# STM32F103.net
KiCad netlist of a schematic drawn in Altium Designer
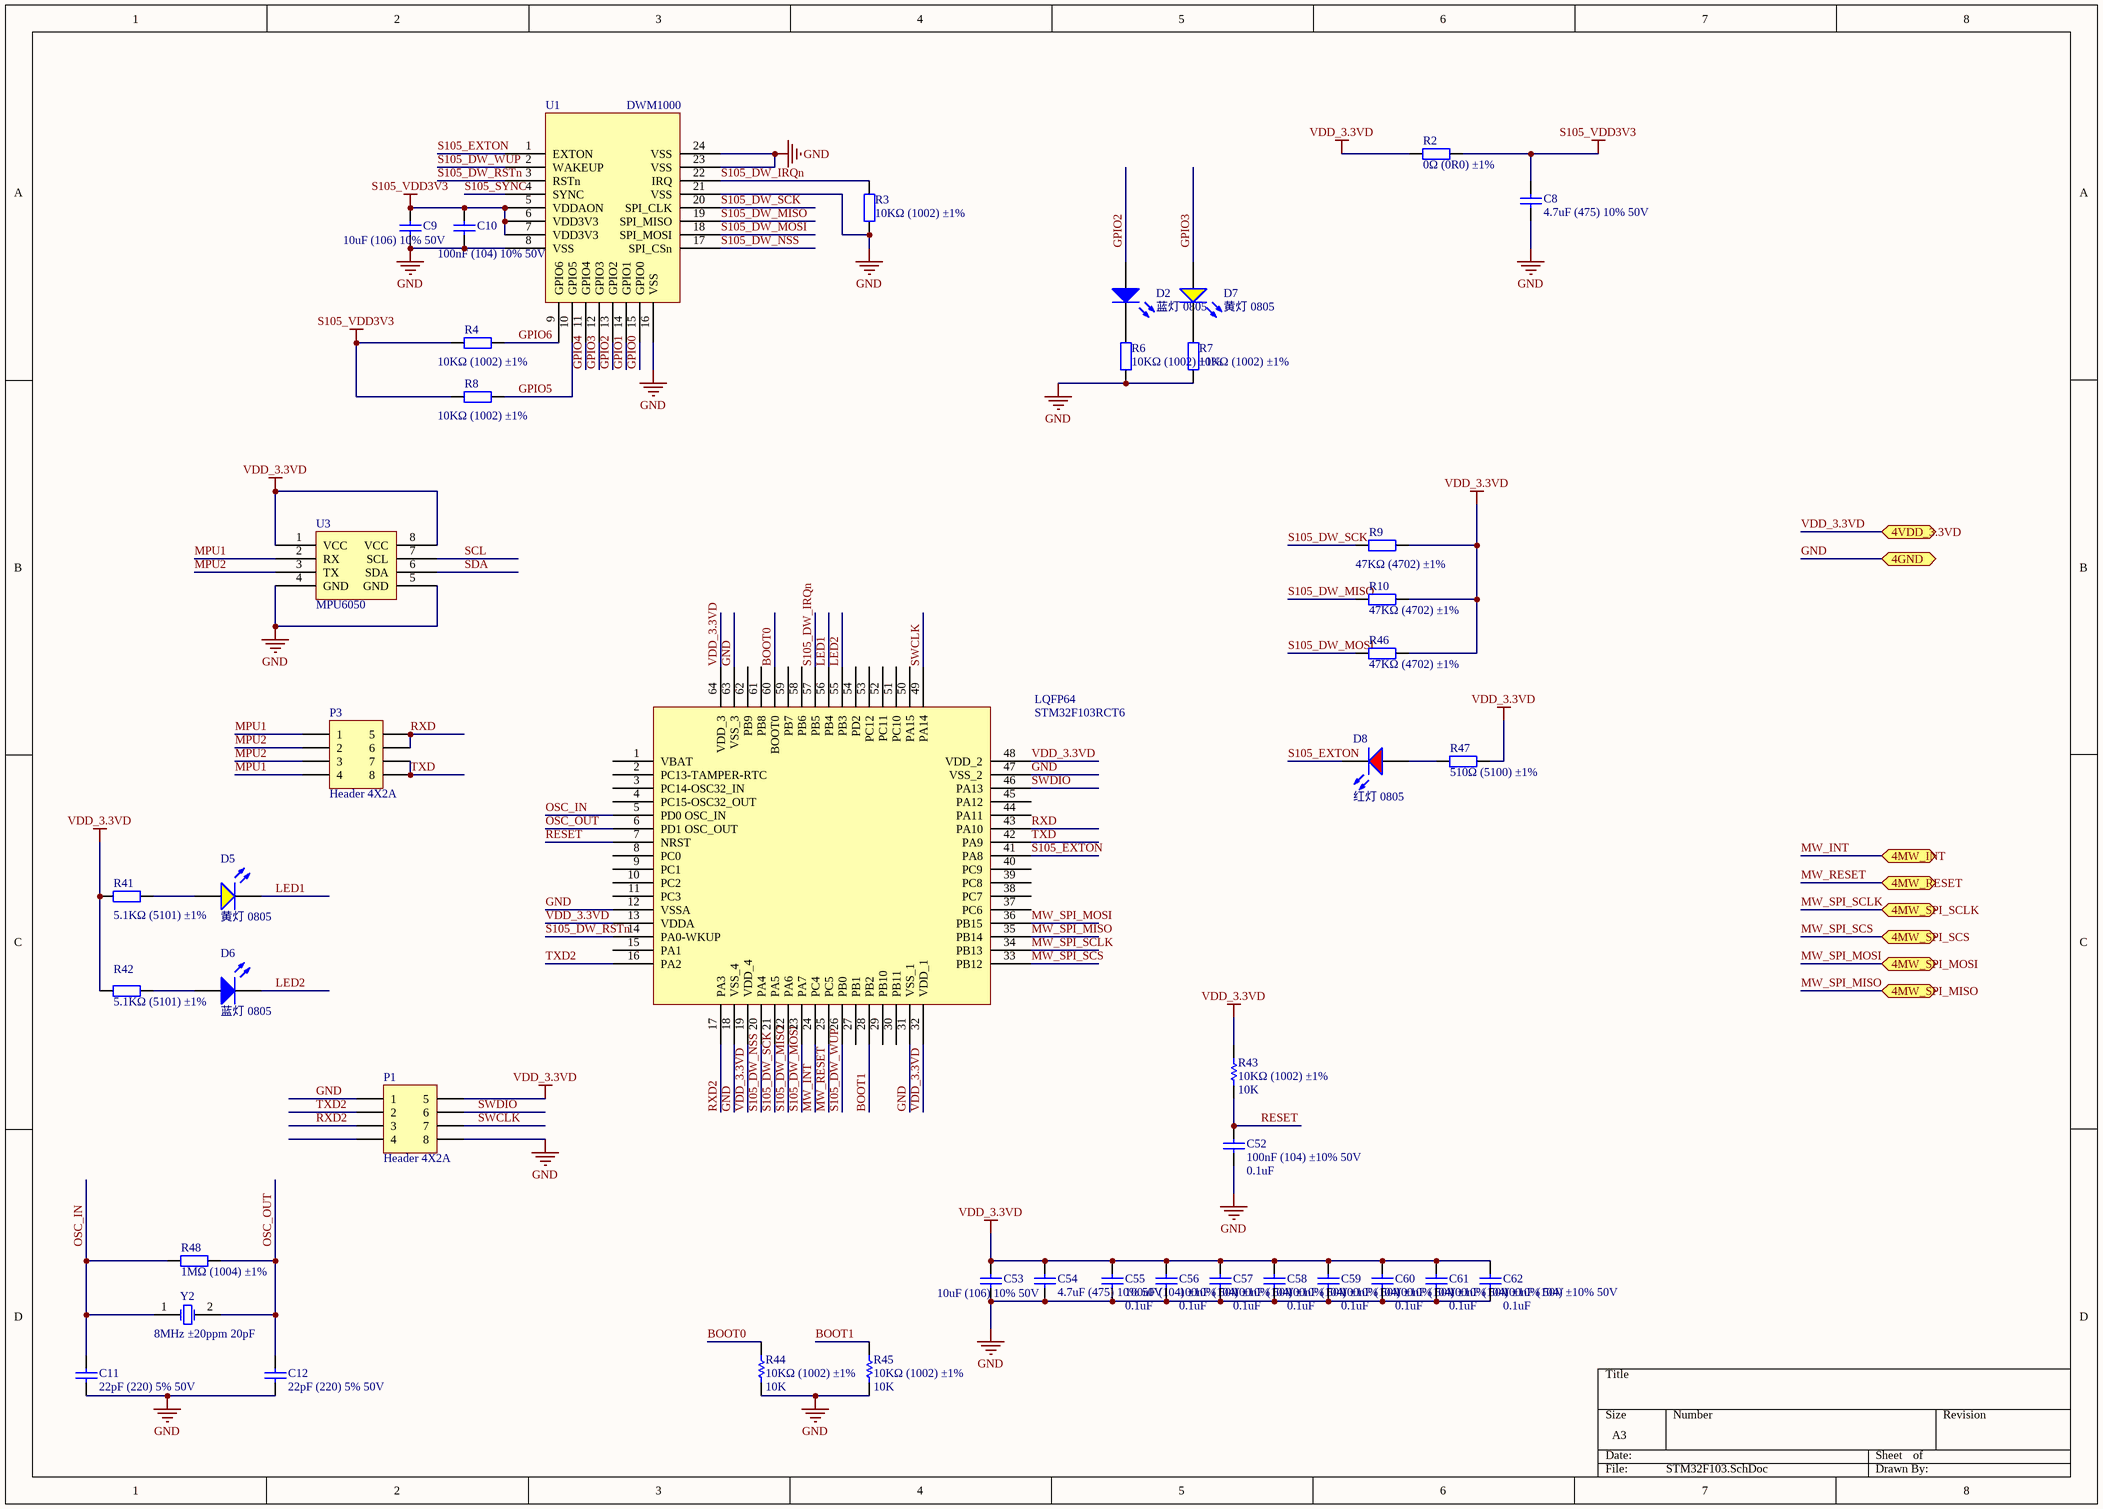
[diagram p0: STM32F103.SchDoc]

(export (version "E")
  (design (tool "Eeschema 10.0.6"))
  (components
    (comp (ref "C8")
      (value "4.7uF (475) 10% 50V")
      (footprint "1206_C")
      (description "贴片电容")
      (libsource (lib "Miscellaneous Devices LC") (part "1206 4.7uF (475) 10% 50V"))
    )
    (comp (ref "C9")
      (value "10uF (106) 10% 50V")
      (footprint "1206_C")
      (description "贴片电容")
      (libsource (lib "Miscellaneous Devices LC") (part "1206 10uF (106) 10% 50V"))
    )
    (comp (ref "C10")
      (value "100nF (104) 10% 50V")
      (footprint "0603_C")
      (description "贴片电容")
      (libsource (lib "Miscellaneous Devices LC") (part "0603 100nF (104) 10% 50V"))
    )
    (comp (ref "C11")
      (value "22pF (220) 5% 50V")
      (footprint "0603_C")
      (description "贴片电容")
      (libsource (lib "Miscellaneous Devices LC") (part "0603 22pF (220) 5% 50V"))
    )
    (comp (ref "C12")
      (value "22pF (220) 5% 50V")
      (footprint "0603_C")
      (description "贴片电容")
      (libsource (lib "Miscellaneous Devices LC") (part "0603 22pF (220) 5% 50V"))
    )
    (comp (ref "C52")
      (value "100nF (104) ±10% 50V")
      (footprint "1608[0603]")
      (description "Capacitor")
      (fields (field (name "ALTIUM_VALUE") "0.1uF") (field (name "PUBLISHER") "Altium Limited"))
      (libsource (lib "Miscellaneous Devices") (part "Cap"))
    )
    (comp (ref "C53")
      (value "10uF (106) 10% 50V")
      (footprint "1206_C")
      (description "贴片电容")
      (libsource (lib "Miscellaneous Devices LC") (part "1206 10uF (106) 10% 50V"))
    )
    (comp (ref "C54")
      (value "4.7uF (475) 10% 50V")
      (footprint "1206_C")
      (description "贴片电容")
      (libsource (lib "Miscellaneous Devices LC") (part "1206 4.7uF (475) 10% 50V"))
    )
    (comp (ref "C55")
      (value "100nF (104) ±10% 50V")
      (footprint "1608[0603]")
      (description "Capacitor")
      (fields (field (name "ALTIUM_VALUE") "0.1uF") (field (name "PUBLISHER") "Altium Limited"))
      (libsource (lib "Miscellaneous Devices") (part "Cap"))
    )
    (comp (ref "C56")
      (value "100nF (104) ±10% 50V")
      (footprint "1608[0603]")
      (description "Capacitor")
      (fields (field (name "ALTIUM_VALUE") "0.1uF") (field (name "PUBLISHER") "Altium Limited"))
      (libsource (lib "Miscellaneous Devices") (part "Cap"))
    )
    (comp (ref "C57")
      (value "100nF (104) ±10% 50V")
      (footprint "1608[0603]")
      (description "Capacitor")
      (fields (field (name "ALTIUM_VALUE") "0.1uF") (field (name "PUBLISHER") "Altium Limited"))
      (libsource (lib "Miscellaneous Devices") (part "Cap"))
    )
    (comp (ref "C58")
      (value "100nF (104) ±10% 50V")
      (footprint "1608[0603]")
      (description "Capacitor")
      (fields (field (name "ALTIUM_VALUE") "0.1uF") (field (name "PUBLISHER") "Altium Limited"))
      (libsource (lib "Miscellaneous Devices") (part "Cap"))
    )
    (comp (ref "C59")
      (value "100nF (104) ±10% 50V")
      (footprint "1608[0603]")
      (description "Capacitor")
      (fields (field (name "ALTIUM_VALUE") "0.1uF") (field (name "PUBLISHER") "Altium Limited"))
      (libsource (lib "Miscellaneous Devices") (part "Cap"))
    )
    (comp (ref "C60")
      (value "100nF (104) ±10% 50V")
      (footprint "1608[0603]")
      (description "Capacitor")
      (fields (field (name "ALTIUM_VALUE") "0.1uF") (field (name "PUBLISHER") "Altium Limited"))
      (libsource (lib "Miscellaneous Devices") (part "Cap"))
    )
    (comp (ref "C61")
      (value "100nF (104) ±10% 50V")
      (footprint "1608[0603]")
      (description "Capacitor")
      (fields (field (name "ALTIUM_VALUE") "0.1uF") (field (name "PUBLISHER") "Altium Limited"))
      (libsource (lib "Miscellaneous Devices") (part "Cap"))
    )
    (comp (ref "C62")
      (value "100nF (104) ±10% 50V")
      (footprint "1608[0603]")
      (description "Capacitor")
      (fields (field (name "ALTIUM_VALUE") "0.1uF") (field (name "PUBLISHER") "Altium Limited"))
      (libsource (lib "Miscellaneous Devices") (part "Cap"))
    )
    (comp (ref "D2")
      (value "蓝灯 0805")
      (footprint "0805_LED_S1")
      (description "发光二极管")
      (libsource (lib "Miscellaneous Devices LC") (part "0805 蓝灯"))
    )
    (comp (ref "D5")
      (value "黄灯 0805")
      (footprint "0805_LED_S1")
      (description "发光二极管")
      (libsource (lib "Miscellaneous Devices LC") (part "0805 黄灯"))
    )
    (comp (ref "D6")
      (value "蓝灯 0805")
      (footprint "0805_LED_S1")
      (description "发光二极管")
      (libsource (lib "Miscellaneous Devices LC") (part "0805 蓝灯"))
    )
    (comp (ref "D7")
      (value "黄灯 0805")
      (footprint "0805_LED_S1")
      (description "发光二极管")
      (libsource (lib "Miscellaneous Devices LC") (part "0805 黄灯"))
    )
    (comp (ref "D8")
      (value "红灯 0805")
      (footprint "0805_LED_S1")
      (description "发光二极管")
      (libsource (lib "Miscellaneous Devices LC") (part "0805 红灯"))
    )
    (comp (ref "LQFP64")
      (value "STM32F103RCT6")
      (footprint "LQFP64")
      (libsource (lib "LS_Schlib1") (part "STM32F103RCT6"))
    )
    (comp (ref "P1")
      (value "Header 4X2A")
      (footprint "HDR2X4_CEN")
      (description "Header, 4-Pin, Dual row")
      (fields (field (name "PUBLISHER") "Altium Limited"))
      (libsource (lib "Miscellaneous Connectors") (part "Header 4X2A"))
    )
    (comp (ref "P3")
      (value "Header 4X2A")
      (footprint "HDR2X4_CEN")
      (description "Header, 4-Pin, Dual row")
      (fields (field (name "PUBLISHER") "Altium Limited"))
      (libsource (lib "Miscellaneous Connectors") (part "Header 4X2A"))
    )
    (comp (ref "R2")
      (value "0Ω (0R0) ±1%")
      (footprint "1206_R")
      (description "贴片电阻")
      (libsource (lib "Miscellaneous Devices LC") (part "1206 0Ω (0R0) 1%"))
    )
    (comp (ref "R3")
      (value "10KΩ (1002) ±1%")
      (footprint "0603_R")
      (description "贴片电阻")
      (libsource (lib "Miscellaneous Devices LC") (part "0603 10KΩ (1002) 1%"))
    )
    (comp (ref "R4")
      (value "10KΩ (1002) ±1%")
      (footprint "0603_R")
      (description "贴片电阻")
      (libsource (lib "") (part "0603 10KΩ (1002) 1%_1"))
    )
    (comp (ref "R6")
      (value "10KΩ (1002) ±1%")
      (footprint "0603_R")
      (description "贴片电阻")
      (libsource (lib "Miscellaneous Devices LC") (part "0603 10KΩ (1002) 1%"))
    )
    (comp (ref "R7")
      (value "10KΩ (1002) ±1%")
      (footprint "0603_R")
      (description "贴片电阻")
      (libsource (lib "Miscellaneous Devices LC") (part "0603 10KΩ (1002) 1%"))
    )
    (comp (ref "R8")
      (value "10KΩ (1002) ±1%")
      (footprint "0603_R")
      (description "贴片电阻")
      (libsource (lib "") (part "0603 10KΩ (1002) 1%_1"))
    )
    (comp (ref "R9")
      (value "47KΩ (4702) ±1%")
      (footprint "0603_R")
      (description "贴片电阻")
      (libsource (lib "Miscellaneous Devices LC") (part "0603 47KΩ (4702) 1%"))
    )
    (comp (ref "R10")
      (value "47KΩ (4702) ±1%")
      (footprint "0603_R")
      (description "贴片电阻")
      (libsource (lib "Miscellaneous Devices LC") (part "0603 47KΩ (4702) 1%"))
    )
    (comp (ref "R41")
      (value "5.1KΩ (5101) ±1%")
      (footprint "0603_R")
      (description "贴片电阻")
      (libsource (lib "Miscellaneous Devices LC") (part "0603 5.1KΩ (5101) 1%"))
    )
    (comp (ref "R42")
      (value "5.1KΩ (5101) ±1%")
      (footprint "0603_R")
      (description "贴片电阻")
      (libsource (lib "Miscellaneous Devices LC") (part "0603 5.1KΩ (5101) 1%"))
    )
    (comp (ref "R43")
      (value "10KΩ (1002) ±1%")
      (footprint "1608[0603]")
      (description "Resistor")
      (fields (field (name "ALTIUM_VALUE") "10K") (field (name "PUBLISHER") "Altium Limited"))
      (libsource (lib "Miscellaneous Devices") (part "Res1"))
    )
    (comp (ref "R44")
      (value "10KΩ (1002) ±1%")
      (footprint "1608[0603]")
      (description "Resistor")
      (fields (field (name "ALTIUM_VALUE") "10K") (field (name "PUBLISHER") "Altium Limited"))
      (libsource (lib "Miscellaneous Devices") (part "Res1"))
    )
    (comp (ref "R45")
      (value "10KΩ (1002) ±1%")
      (footprint "1608[0603]")
      (description "Resistor")
      (fields (field (name "ALTIUM_VALUE") "10K") (field (name "PUBLISHER") "Altium Limited"))
      (libsource (lib "Miscellaneous Devices") (part "Res1"))
    )
    (comp (ref "R46")
      (value "47KΩ (4702) ±1%")
      (footprint "0603_R")
      (description "贴片电阻")
      (libsource (lib "Miscellaneous Devices LC") (part "0603 47KΩ (4702) 1%"))
    )
    (comp (ref "R47")
      (value "510Ω (5100) ±1%")
      (footprint "0603_R")
      (description "贴片电阻")
      (libsource (lib "Miscellaneous Devices LC") (part "0603 510Ω (5100) 1%"))
    )
    (comp (ref "R48")
      (value "1MΩ (1004) ±1%")
      (footprint "0603_R")
      (description "贴片电阻")
      (libsource (lib "Miscellaneous Devices LC") (part "0603 1MΩ (1004) 1%"))
    )
    (comp (ref "U1")
      (value "DWM1000")
      (footprint "DWM1000")
      (libsource (lib "UWB_Location") (part "DWM1000"))
    )
    (comp (ref "U3") (value "MPU6050") (footprint "MPU6050") (libsource (lib "LS_Schlib1") (part "MPU6050")))
    (comp (ref "Y2")
      (value "8MHz ±20ppm 20pF")
      (footprint "SMD-5032_2P")
      (description "贴片晶振")
      (libsource (lib "Miscellaneous Devices LC") (part "SMD-5032_2P 8MHz 20ppm 20pF"))
    )
  )
  (nets
    (net (code "1") (name "/BOOT0") (class "Default")
      (node (ref "LQFP64") (pin "60") (pinfunction "BOOT0_60") (pintype "passive"))
      (node (ref "R44") (pin "2") (pinfunction "2_2") (pintype "passive"))
    )
    (net (code "2") (name "/BOOT1") (class "Default")
      (node (ref "LQFP64") (pin "28") (pinfunction "PB2_28") (pintype "passive"))
      (node (ref "R45") (pin "2") (pinfunction "2_2") (pintype "passive"))
    )
    (net (code "3") (name "/GPIO0") (class "Default")
      (node (ref "U1") (pin "15") (pinfunction "GPIO0_15") (pintype "passive"))
    )
    (net (code "4") (name "/GPIO1") (class "Default")
      (node (ref "U1") (pin "14") (pinfunction "GPIO1_14") (pintype "passive"))
    )
    (net (code "5") (name "/GPIO2") (class "Default")
      (node (ref "D2") (pin "A") (pinfunction "A_A") (pintype "passive"))
      (node (ref "U1") (pin "13") (pinfunction "GPIO2_13") (pintype "passive"))
    )
    (net (code "6") (name "/GPIO3") (class "Default")
      (node (ref "D7") (pin "A") (pinfunction "A_A") (pintype "passive"))
      (node (ref "U1") (pin "12") (pinfunction "GPIO3_12") (pintype "passive"))
    )
    (net (code "7") (name "/GPIO4") (class "Default")
      (node (ref "U1") (pin "11") (pinfunction "GPIO4_11") (pintype "passive"))
    )
    (net (code "8") (name "/GPIO5") (class "Default")
      (node (ref "R8") (pin "2") (pinfunction "2_2") (pintype "passive"))
      (node (ref "U1") (pin "10") (pinfunction "GPIO5_10") (pintype "passive"))
    )
    (net (code "9") (name "/GPIO6") (class "Default")
      (node (ref "R4") (pin "2") (pinfunction "2_2") (pintype "passive"))
      (node (ref "U1") (pin "9") (pinfunction "GPIO6_9") (pintype "passive"))
    )
    (net (code "10") (name "/LED1") (class "Default")
      (node (ref "D5") (pin "K") (pinfunction "K_K") (pintype "passive"))
      (node (ref "LQFP64") (pin "56") (pinfunction "PB4_56") (pintype "passive"))
    )
    (net (code "11") (name "/LED2") (class "Default")
      (node (ref "D6") (pin "K") (pinfunction "K_K") (pintype "passive"))
      (node (ref "LQFP64") (pin "55") (pinfunction "PB3_55") (pintype "passive"))
    )
    (net (code "12") (name "/MPU1") (class "Default")
      (node (ref "P3") (pin "1") (pinfunction "1_1") (pintype "passive"))
      (node (ref "P3") (pin "4") (pinfunction "4_4") (pintype "passive"))
      (node (ref "U3") (pin "2") (pinfunction "RX_2") (pintype "passive"))
    )
    (net (code "13") (name "/MPU2") (class "Default")
      (node (ref "P3") (pin "2") (pinfunction "2_2") (pintype "passive"))
      (node (ref "P3") (pin "3") (pinfunction "3_3") (pintype "passive"))
      (node (ref "U3") (pin "3") (pinfunction "TX_3") (pintype "passive"))
    )
    (net (code "14") (name "/MW_INT") (class "Default")
      (node (ref "LQFP64") (pin "24") (pinfunction "PC4_24") (pintype "passive"))
    )
    (net (code "15") (name "/MW_RESET") (class "Default")
      (node (ref "LQFP64") (pin "25") (pinfunction "PC5_25") (pintype "passive"))
    )
    (net (code "16") (name "/MW_SPI_MISO") (class "Default")
      (node (ref "LQFP64") (pin "35") (pinfunction "PB14_35") (pintype "passive"))
    )
    (net (code "17") (name "/MW_SPI_MOSI") (class "Default")
      (node (ref "LQFP64") (pin "36") (pinfunction "PB15_36") (pintype "passive"))
    )
    (net (code "18") (name "/MW_SPI_SCLK") (class "Default")
      (node (ref "LQFP64") (pin "34") (pinfunction "PB13_34") (pintype "passive"))
    )
    (net (code "19") (name "/MW_SPI_SCS") (class "Default")
      (node (ref "LQFP64") (pin "33") (pinfunction "PB12_33") (pintype "passive"))
    )
    (net (code "20") (name "/OSC_IN") (class "Default")
      (node (ref "C11") (pin "2") (pinfunction "2_2") (pintype "passive"))
      (node (ref "LQFP64") (pin "5") (pinfunction "PD0_OSC_IN_5") (pintype "passive"))
      (node (ref "R48") (pin "1") (pinfunction "1_1") (pintype "passive"))
      (node (ref "Y2") (pin "1") (pinfunction "OSC1_1") (pintype "passive"))
    )
    (net (code "21") (name "/OSC_OUT") (class "Default")
      (node (ref "C12") (pin "2") (pinfunction "2_2") (pintype "passive"))
      (node (ref "LQFP64") (pin "6") (pinfunction "PD1_OSC_OUT_6") (pintype "passive"))
      (node (ref "R48") (pin "2") (pinfunction "2_2") (pintype "passive"))
      (node (ref "Y2") (pin "2") (pinfunction "OSC2_2") (pintype "passive"))
    )
    (net (code "22") (name "/RESET") (class "Default")
      (node (ref "C52") (pin "2") (pinfunction "2_2") (pintype "passive"))
      (node (ref "LQFP64") (pin "7") (pinfunction "NRST_7") (pintype "passive"))
      (node (ref "R43") (pin "1") (pinfunction "1_1") (pintype "passive"))
    )
    (net (code "23") (name "/RXD") (class "Default")
      (node (ref "LQFP64") (pin "43") (pinfunction "PA10_43") (pintype "passive"))
      (node (ref "P3") (pin "5") (pinfunction "5_5") (pintype "passive"))
      (node (ref "P3") (pin "6") (pinfunction "6_6") (pintype "passive"))
    )
    (net (code "24") (name "/RXD2") (class "Default")
      (node (ref "LQFP64") (pin "17") (pinfunction "PA3_17") (pintype "passive"))
      (node (ref "P1") (pin "3") (pinfunction "3_3") (pintype "passive"))
    )
    (net (code "25") (name "/S105_DW_IRQn") (class "Default")
      (node (ref "LQFP64") (pin "57") (pinfunction "PB5_57") (pintype "passive"))
      (node (ref "R3") (pin "2") (pinfunction "2_2") (pintype "passive"))
      (node (ref "U1") (pin "22") (pinfunction "IRQ_22") (pintype "passive"))
    )
    (net (code "26") (name "/S105_DW_MISO") (class "Default")
      (node (ref "LQFP64") (pin "22") (pinfunction "PA6_22") (pintype "passive"))
      (node (ref "R10") (pin "1") (pinfunction "1_1") (pintype "passive"))
      (node (ref "U1") (pin "19") (pinfunction "SPI_MISO_19") (pintype "passive"))
    )
    (net (code "27") (name "/S105_DW_MOSI") (class "Default")
      (node (ref "LQFP64") (pin "23") (pinfunction "PA7_23") (pintype "passive"))
      (node (ref "R46") (pin "1") (pinfunction "1_1") (pintype "passive"))
      (node (ref "U1") (pin "18") (pinfunction "SPI_MOSI_18") (pintype "passive"))
    )
    (net (code "28") (name "/S105_DW_NSS") (class "Default")
      (node (ref "LQFP64") (pin "20") (pinfunction "PA4_20") (pintype "passive"))
      (node (ref "U1") (pin "17") (pinfunction "SPI_CSn_17") (pintype "passive"))
    )
    (net (code "29") (name "/S105_DW_RSTn") (class "Default")
      (node (ref "LQFP64") (pin "14") (pinfunction "PA0-WKUP_14") (pintype "passive"))
      (node (ref "U1") (pin "3") (pinfunction "RSTn_3") (pintype "passive"))
    )
    (net (code "30") (name "/S105_DW_SCK") (class "Default")
      (node (ref "LQFP64") (pin "21") (pinfunction "PA5_21") (pintype "passive"))
      (node (ref "R9") (pin "1") (pinfunction "1_1") (pintype "passive"))
      (node (ref "U1") (pin "20") (pinfunction "SPI_CLK_20") (pintype "passive"))
    )
    (net (code "31") (name "/S105_DW_WUP") (class "Default")
      (node (ref "LQFP64") (pin "26") (pinfunction "PB0_26") (pintype "passive"))
      (node (ref "U1") (pin "2") (pinfunction "WAKEUP_2") (pintype "passive"))
    )
    (net (code "32") (name "/S105_EXTON") (class "Default")
      (node (ref "D8") (pin "K") (pinfunction "K_K") (pintype "passive"))
      (node (ref "LQFP64") (pin "41") (pinfunction "PA8_41") (pintype "passive"))
      (node (ref "U1") (pin "1") (pinfunction "EXTON_1") (pintype "passive"))
    )
    (net (code "33") (name "/S105_SYNC") (class "Default")
      (node (ref "U1") (pin "4") (pinfunction "SYNC_4") (pintype "passive"))
    )
    (net (code "34") (name "/SCL") (class "Default")
      (node (ref "U3") (pin "7") (pinfunction "SCL_7") (pintype "passive"))
    )
    (net (code "35") (name "/SDA") (class "Default")
      (node (ref "U3") (pin "6") (pinfunction "SDA_6") (pintype "passive"))
    )
    (net (code "36") (name "/SWCLK") (class "Default")
      (node (ref "LQFP64") (pin "49") (pinfunction "PA14_49") (pintype "passive"))
      (node (ref "P1") (pin "7") (pinfunction "7_7") (pintype "passive"))
    )
    (net (code "37") (name "/SWDIO") (class "Default")
      (node (ref "LQFP64") (pin "46") (pinfunction "PA13_46") (pintype "passive"))
      (node (ref "P1") (pin "6") (pinfunction "6_6") (pintype "passive"))
    )
    (net (code "38") (name "/TXD") (class "Default")
      (node (ref "LQFP64") (pin "42") (pinfunction "PA9_42") (pintype "passive"))
      (node (ref "P3") (pin "7") (pinfunction "7_7") (pintype "passive"))
      (node (ref "P3") (pin "8") (pinfunction "8_8") (pintype "passive"))
    )
    (net (code "39") (name "/TXD2") (class "Default")
      (node (ref "LQFP64") (pin "16") (pinfunction "PA2_16") (pintype "passive"))
      (node (ref "P1") (pin "2") (pinfunction "2_2") (pintype "passive"))
    )
    (net (code "40") (name "GND") (class "Default")
      (node (ref "C10") (pin "1") (pinfunction "1_1") (pintype "passive"))
      (node (ref "C11") (pin "1") (pinfunction "1_1") (pintype "passive"))
      (node (ref "C12") (pin "1") (pinfunction "1_1") (pintype "passive"))
      (node (ref "C52") (pin "1") (pinfunction "1_1") (pintype "passive"))
      (node (ref "C53") (pin "1") (pinfunction "1_1") (pintype "passive"))
      (node (ref "C54") (pin "1") (pinfunction "1_1") (pintype "passive"))
      (node (ref "C55") (pin "1") (pinfunction "1_1") (pintype "passive"))
      (node (ref "C56") (pin "1") (pinfunction "1_1") (pintype "passive"))
      (node (ref "C57") (pin "1") (pinfunction "1_1") (pintype "passive"))
      (node (ref "C58") (pin "1") (pinfunction "1_1") (pintype "passive"))
      (node (ref "C59") (pin "1") (pinfunction "1_1") (pintype "passive"))
      (node (ref "C60") (pin "1") (pinfunction "1_1") (pintype "passive"))
      (node (ref "C61") (pin "1") (pinfunction "1_1") (pintype "passive"))
      (node (ref "C62") (pin "1") (pinfunction "1_1") (pintype "passive"))
      (node (ref "C8") (pin "1") (pinfunction "1_1") (pintype "passive"))
      (node (ref "C9") (pin "1") (pinfunction "1_1") (pintype "passive"))
      (node (ref "LQFP64") (pin "12") (pinfunction "VSSA_12") (pintype "passive"))
      (node (ref "LQFP64") (pin "18") (pinfunction "VSS_4_18") (pintype "passive"))
      (node (ref "LQFP64") (pin "31") (pinfunction "VSS_1_31") (pintype "passive"))
      (node (ref "LQFP64") (pin "47") (pinfunction "VSS_2_47") (pintype "passive"))
      (node (ref "LQFP64") (pin "63") (pinfunction "VSS_3_63") (pintype "passive"))
      (node (ref "P1") (pin "1") (pinfunction "1_1") (pintype "passive"))
      (node (ref "P1") (pin "8") (pinfunction "8_8") (pintype "passive"))
      (node (ref "R3") (pin "1") (pinfunction "1_1") (pintype "passive"))
      (node (ref "R44") (pin "1") (pinfunction "1_1") (pintype "passive"))
      (node (ref "R45") (pin "1") (pinfunction "1_1") (pintype "passive"))
      (node (ref "R6") (pin "1") (pinfunction "1_1") (pintype "passive"))
      (node (ref "R7") (pin "1") (pinfunction "1_1") (pintype "passive"))
      (node (ref "U1") (pin "16") (pinfunction "VSS_16") (pintype "passive"))
      (node (ref "U1") (pin "21") (pinfunction "VSS_21") (pintype "passive"))
      (node (ref "U1") (pin "23") (pinfunction "VSS_23") (pintype "passive"))
      (node (ref "U1") (pin "24") (pinfunction "VSS_24") (pintype "passive"))
      (node (ref "U1") (pin "8") (pinfunction "VSS_8") (pintype "passive"))
      (node (ref "U3") (pin "4") (pinfunction "GND_4") (pintype "passive"))
      (node (ref "U3") (pin "5") (pinfunction "GND_5") (pintype "passive"))
    )
    (net (code "41") (name "Net-(D2-PadK)") (class "Default")
      (node (ref "D2") (pin "K") (pinfunction "K_K") (pintype "passive"))
      (node (ref "R6") (pin "2") (pinfunction "2_2") (pintype "passive"))
    )
    (net (code "42") (name "Net-(D5-PadA)") (class "Default")
      (node (ref "D5") (pin "A") (pinfunction "A_A") (pintype "passive"))
      (node (ref "R41") (pin "2") (pinfunction "2_2") (pintype "passive"))
    )
    (net (code "43") (name "Net-(D6-PadA)") (class "Default")
      (node (ref "D6") (pin "A") (pinfunction "A_A") (pintype "passive"))
      (node (ref "R42") (pin "2") (pinfunction "2_2") (pintype "passive"))
    )
    (net (code "44") (name "Net-(D7-PadK)") (class "Default")
      (node (ref "D7") (pin "K") (pinfunction "K_K") (pintype "passive"))
      (node (ref "R7") (pin "2") (pinfunction "2_2") (pintype "passive"))
    )
    (net (code "45") (name "Net-(D8-PadA)") (class "Default")
      (node (ref "D8") (pin "A") (pinfunction "A_A") (pintype "passive"))
      (node (ref "R47") (pin "1") (pinfunction "1_1") (pintype "passive"))
    )
    (net (code "46") (name "S105_VDD3V3") (class "Default")
      (node (ref "C10") (pin "2") (pinfunction "2_2") (pintype "passive"))
      (node (ref "C8") (pin "2") (pinfunction "2_2") (pintype "passive"))
      (node (ref "C9") (pin "2") (pinfunction "2_2") (pintype "passive"))
      (node (ref "R2") (pin "2") (pinfunction "2_2") (pintype "passive"))
      (node (ref "R4") (pin "1") (pinfunction "1_1") (pintype "passive"))
      (node (ref "R8") (pin "1") (pinfunction "1_1") (pintype "passive"))
      (node (ref "U1") (pin "5") (pinfunction "VDDAON_5") (pintype "passive"))
      (node (ref "U1") (pin "6") (pinfunction "VDD3V3_6") (pintype "passive"))
      (node (ref "U1") (pin "7") (pinfunction "VDD3V3_7") (pintype "passive"))
    )
    (net (code "47") (name "VDD_3.3VD") (class "Default")
      (node (ref "C53") (pin "2") (pinfunction "2_2") (pintype "passive"))
      (node (ref "C54") (pin "2") (pinfunction "2_2") (pintype "passive"))
      (node (ref "C55") (pin "2") (pinfunction "2_2") (pintype "passive"))
      (node (ref "C56") (pin "2") (pinfunction "2_2") (pintype "passive"))
      (node (ref "C57") (pin "2") (pinfunction "2_2") (pintype "passive"))
      (node (ref "C58") (pin "2") (pinfunction "2_2") (pintype "passive"))
      (node (ref "C59") (pin "2") (pinfunction "2_2") (pintype "passive"))
      (node (ref "C60") (pin "2") (pinfunction "2_2") (pintype "passive"))
      (node (ref "C61") (pin "2") (pinfunction "2_2") (pintype "passive"))
      (node (ref "C62") (pin "2") (pinfunction "2_2") (pintype "passive"))
      (node (ref "LQFP64") (pin "13") (pinfunction "VDDA_13") (pintype "passive"))
      (node (ref "LQFP64") (pin "19") (pinfunction "VDD_4_19") (pintype "passive"))
      (node (ref "LQFP64") (pin "32") (pinfunction "VDD_1_32") (pintype "passive"))
      (node (ref "LQFP64") (pin "48") (pinfunction "VDD_2_48") (pintype "passive"))
      (node (ref "LQFP64") (pin "64") (pinfunction "VDD_3_64") (pintype "passive"))
      (node (ref "P1") (pin "5") (pinfunction "5_5") (pintype "passive"))
      (node (ref "R10") (pin "2") (pinfunction "2_2") (pintype "passive"))
      (node (ref "R2") (pin "1") (pinfunction "1_1") (pintype "passive"))
      (node (ref "R41") (pin "1") (pinfunction "1_1") (pintype "passive"))
      (node (ref "R42") (pin "1") (pinfunction "1_1") (pintype "passive"))
      (node (ref "R43") (pin "2") (pinfunction "2_2") (pintype "passive"))
      (node (ref "R46") (pin "2") (pinfunction "2_2") (pintype "passive"))
      (node (ref "R47") (pin "2") (pinfunction "2_2") (pintype "passive"))
      (node (ref "R9") (pin "2") (pinfunction "2_2") (pintype "passive"))
      (node (ref "U3") (pin "1") (pinfunction "VCC_1") (pintype "passive"))
      (node (ref "U3") (pin "8") (pinfunction "VCC_8") (pintype "passive"))
    )
    (net (code "48") (name "unconnected-(LQFP64-PA1-Pad15)") (class "Default")
      (node (ref "LQFP64") (pin "15") (pinfunction "PA1_15") (pintype "passive"))
    )
    (net (code "49") (name "unconnected-(LQFP64-PA11-Pad44)") (class "Default")
      (node (ref "LQFP64") (pin "44") (pinfunction "PA11_44") (pintype "passive"))
    )
    (net (code "50") (name "unconnected-(LQFP64-PA12-Pad45)") (class "Default")
      (node (ref "LQFP64") (pin "45") (pinfunction "PA12_45") (pintype "passive"))
    )
    (net (code "51") (name "unconnected-(LQFP64-PA15-Pad50)") (class "Default")
      (node (ref "LQFP64") (pin "50") (pinfunction "PA15_50") (pintype "passive"))
    )
    (net (code "52") (name "unconnected-(LQFP64-PB1-Pad27)") (class "Default")
      (node (ref "LQFP64") (pin "27") (pinfunction "PB1_27") (pintype "passive"))
    )
    (net (code "53") (name "unconnected-(LQFP64-PB6-Pad58)") (class "Default")
      (node (ref "LQFP64") (pin "58") (pinfunction "PB6_58") (pintype "passive"))
    )
    (net (code "54") (name "unconnected-(LQFP64-PB7-Pad59)") (class "Default")
      (node (ref "LQFP64") (pin "59") (pinfunction "PB7_59") (pintype "passive"))
    )
    (net (code "55") (name "unconnected-(LQFP64-PB8-Pad61)") (class "Default")
      (node (ref "LQFP64") (pin "61") (pinfunction "PB8_61") (pintype "passive"))
    )
    (net (code "56") (name "unconnected-(LQFP64-PB9-Pad62)") (class "Default")
      (node (ref "LQFP64") (pin "62") (pinfunction "PB9_62") (pintype "passive"))
    )
    (net (code "57") (name "unconnected-(LQFP64-PB10-Pad29)") (class "Default")
      (node (ref "LQFP64") (pin "29") (pinfunction "PB10_29") (pintype "passive"))
    )
    (net (code "58") (name "unconnected-(LQFP64-PB11-Pad30)") (class "Default")
      (node (ref "LQFP64") (pin "30") (pinfunction "PB11_30") (pintype "passive"))
    )
    (net (code "59") (name "unconnected-(LQFP64-PC0-Pad8)") (class "Default")
      (node (ref "LQFP64") (pin "8") (pinfunction "PC0_8") (pintype "passive"))
    )
    (net (code "60") (name "unconnected-(LQFP64-PC1-Pad9)") (class "Default")
      (node (ref "LQFP64") (pin "9") (pinfunction "PC1_9") (pintype "passive"))
    )
    (net (code "61") (name "unconnected-(LQFP64-PC2-Pad10)") (class "Default")
      (node (ref "LQFP64") (pin "10") (pinfunction "PC2_10") (pintype "passive"))
    )
    (net (code "62") (name "unconnected-(LQFP64-PC3-Pad11)") (class "Default")
      (node (ref "LQFP64") (pin "11") (pinfunction "PC3_11") (pintype "passive"))
    )
    (net (code "63") (name "unconnected-(LQFP64-PC6-Pad37)") (class "Default")
      (node (ref "LQFP64") (pin "37") (pinfunction "PC6_37") (pintype "passive"))
    )
    (net (code "64") (name "unconnected-(LQFP64-PC7-Pad38)") (class "Default")
      (node (ref "LQFP64") (pin "38") (pinfunction "PC7_38") (pintype "passive"))
    )
    (net (code "65") (name "unconnected-(LQFP64-PC8-Pad39)") (class "Default")
      (node (ref "LQFP64") (pin "39") (pinfunction "PC8_39") (pintype "passive"))
    )
    (net (code "66") (name "unconnected-(LQFP64-PC9-Pad40)") (class "Default")
      (node (ref "LQFP64") (pin "40") (pinfunction "PC9_40") (pintype "passive"))
    )
    (net (code "67") (name "unconnected-(LQFP64-PC10-Pad51)") (class "Default")
      (node (ref "LQFP64") (pin "51") (pinfunction "PC10_51") (pintype "passive"))
    )
    (net (code "68") (name "unconnected-(LQFP64-PC11-Pad52)") (class "Default")
      (node (ref "LQFP64") (pin "52") (pinfunction "PC11_52") (pintype "passive"))
    )
    (net (code "69") (name "unconnected-(LQFP64-PC12-Pad53)") (class "Default")
      (node (ref "LQFP64") (pin "53") (pinfunction "PC12_53") (pintype "passive"))
    )
    (net (code "70") (name "unconnected-(LQFP64-PC13-TAMPER-RTC-Pad2)") (class "Default")
      (node (ref "LQFP64") (pin "2") (pinfunction "PC13-TAMPER-RTC_2") (pintype "passive"))
    )
    (net (code "71") (name "unconnected-(LQFP64-PC14-OSC32_IN-Pad3)") (class "Default")
      (node (ref "LQFP64") (pin "3") (pinfunction "PC14-OSC32_IN_3") (pintype "passive"))
    )
    (net (code "72") (name "unconnected-(LQFP64-PC15-OSC32_OUT-Pad4)") (class "Default")
      (node (ref "LQFP64") (pin "4") (pinfunction "PC15-OSC32_OUT_4") (pintype "passive"))
    )
    (net (code "73") (name "unconnected-(LQFP64-PD2-Pad54)") (class "Default")
      (node (ref "LQFP64") (pin "54") (pinfunction "PD2_54") (pintype "passive"))
    )
    (net (code "74") (name "unconnected-(LQFP64-VBAT-Pad1)") (class "Default")
      (node (ref "LQFP64") (pin "1") (pinfunction "VBAT_1") (pintype "passive"))
    )
    (net (code "75") (name "unconnected-(P1-Pad4)") (class "Default")
      (node (ref "P1") (pin "4") (pinfunction "4_4") (pintype "passive"))
    )
  )
)
